# BPS_PowerInput_v1-0.net
KiCad netlist of a schematic drawn in Altium Designer
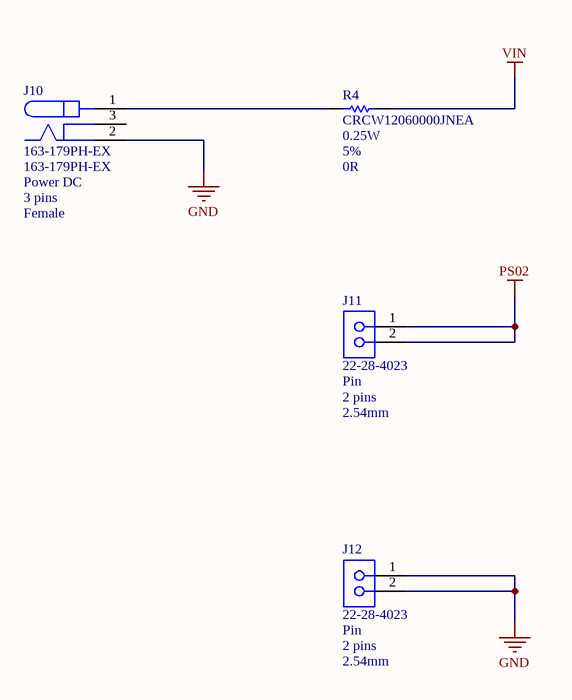
[diagram p0: BPS_PowerInput_v1-0.SchDoc]

(export (version "E")
  (design (tool "Eeschema 10.0.6"))
  (components
    (comp (ref "J10")
      (value "163-179PH-EX")
      (footprint "PowerJack_2.1_5.5")
      (description "DC Power Connectors PCB 2.1MM")
      (fields
        (field (name "PARTNUMBER1") "163-179PH-EX")
        (field (name "TYPE") "Power DC")
        (field (name "PINS") "3 pins")
        (field (name "GENDER") "Female")
        (field (name "PUBLISHER") "Lucas Moraes")
      )
      (libsource (lib "PowerDCConnector") (part "163-179PH-EX"))
    )
    (comp (ref "J11")
      (value "22-28-4023")
      (footprint "CONSIL02STRMALE_100_100")
      (description "Headers & Wire Housings 02 MODII HDR SRST B/A .100CL")
      (fields
        (field (name "PARTNUMBER1") "22-28-4023")
        (field (name "TYPE") "Pin")
        (field (name "PINS") "2 pins")
        (field (name "PITCH") "2.54mm")
        (field (name "PUBLISHER") "Lucas Moraes")
      )
      (libsource (lib "Header PinSocket") (part "22-28-4023"))
    )
    (comp (ref "J12")
      (value "22-28-4023")
      (footprint "CONSIL02STRMALE_100_100")
      (description "Headers & Wire Housings 02 MODII HDR SRST B/A .100CL")
      (fields
        (field (name "PARTNUMBER1") "22-28-4023")
        (field (name "TYPE") "Pin")
        (field (name "PINS") "2 pins")
        (field (name "PITCH") "2.54mm")
        (field (name "PUBLISHER") "Lucas Moraes")
      )
      (libsource (lib "Header PinSocket") (part "22-28-4023"))
    )
    (comp (ref "R4")
      (value "0R")
      (footprint "RES1206")
      (description "Thick Film Chip Resistors with CECC Approval,  available with Established Reliability")
      (fields
        (field (name "PARTNUMBER1") "CRCW12060000JNEA")
        (field (name "POWER") "0.25W")
        (field (name "TOLERANCE") "5%")
        (field (name "Comment") "Chip Resistor")
        (field (name "PUBLISHER") "Lucas Moraes")
      )
      (libsource (lib "ResistorsFixed") (part "CRCW1206"))
    )
  )
  (nets
    (net (code "1") (name "GND") (class "Default")
      (node (ref "J10") (pin "2") (pinfunction "2_2") (pintype "passive"))
      (node (ref "J12") (pin "1") (pinfunction "1_1") (pintype "passive"))
      (node (ref "J12") (pin "2") (pinfunction "2_2") (pintype "passive"))
    )
    (net (code "2") (name "Net-(J10-Pad1)") (class "Default")
      (node (ref "J10") (pin "1") (pinfunction "1_1") (pintype "passive"))
      (node (ref "R4") (pin "2") (pinfunction "2_2") (pintype "passive"))
    )
    (net (code "3") (name "PS02") (class "Default")
      (node (ref "J11") (pin "1") (pinfunction "1_1") (pintype "passive"))
      (node (ref "J11") (pin "2") (pinfunction "2_2") (pintype "passive"))
    )
    (net (code "4") (name "VIN") (class "Default")
      (node (ref "R4") (pin "1") (pinfunction "1_1") (pintype "passive"))
    )
    (net (code "5") (name "unconnected-(J10-Pad3)") (class "Default")
      (node (ref "J10") (pin "3") (pinfunction "3_3") (pintype "passive"))
    )
  )
)
